# USBdevice.net
KiCad netlist of a schematic drawn in Altium Designer
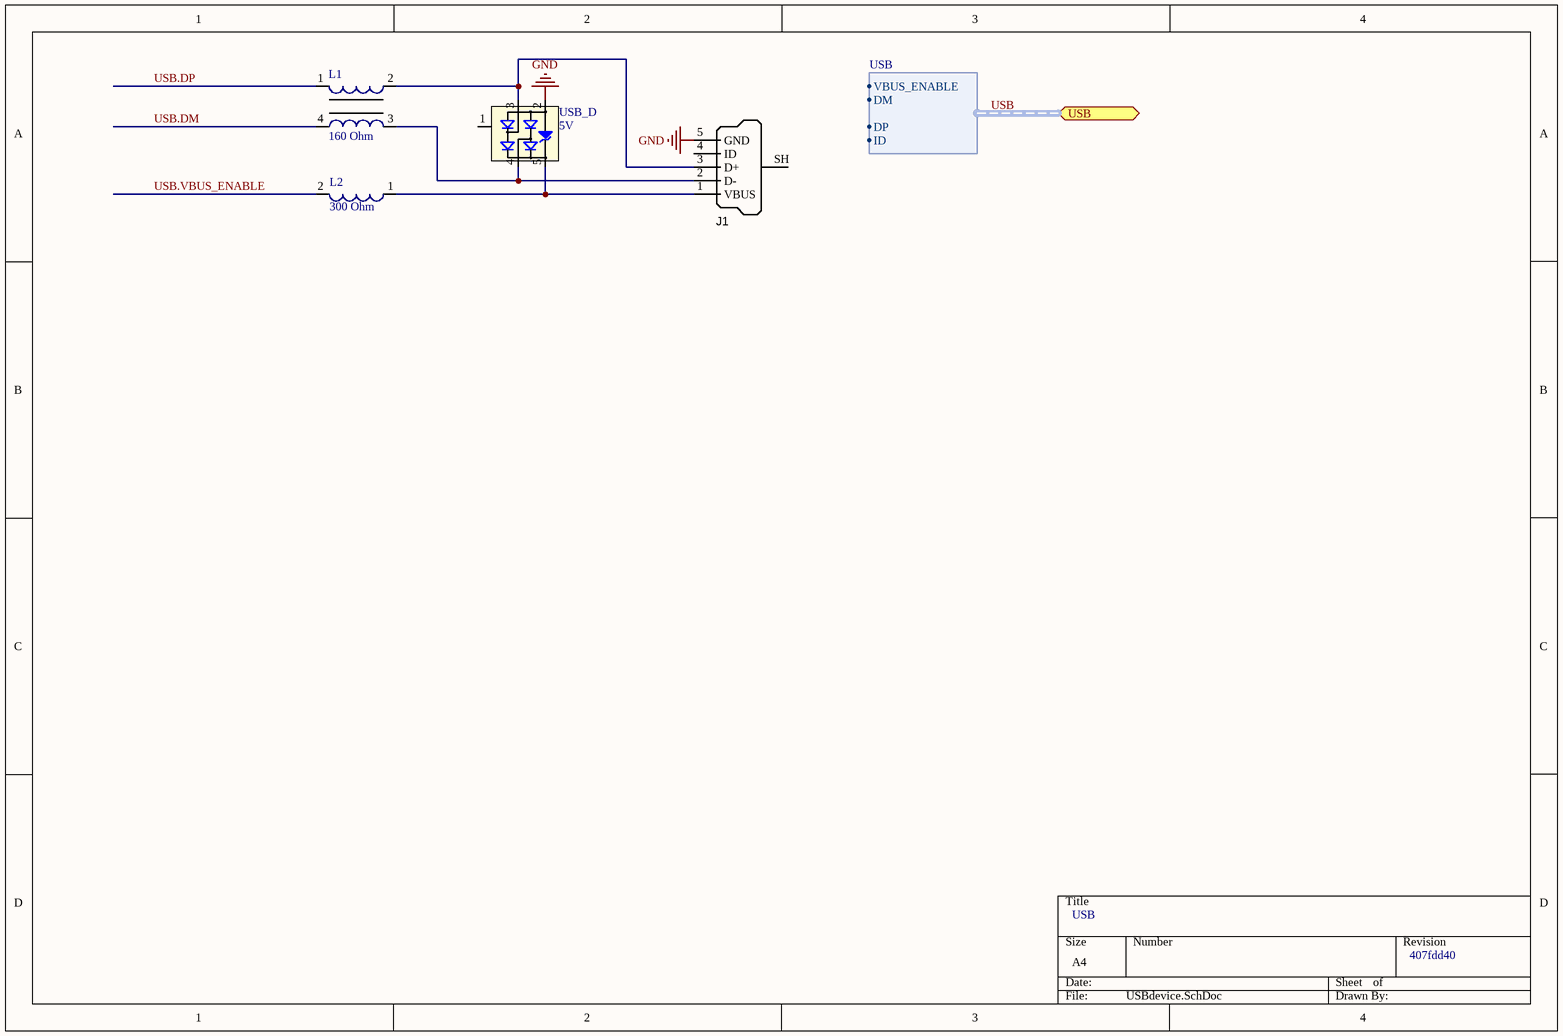
[diagram p0: USBdevice.SchDoc]

(export (version "E")
  (design (tool "Eeschema 10.0.6"))
  (components
    (comp (ref "J1")
      (value "USB Micro Type B")
      (footprint "PBL - SMD Packages:USB_Micro-B_FCI_SMD")
      (description "Connector SMD-THD USB Micro Type B middle mount")
      (libsource (lib "PBL - Connectors") (part "USB_Micro_TypeB_FCI"))
    )
    (comp (ref "L1")
      (value "160 Ohm")
      (footprint "WE-CNSW, 1206")
      (description "SMD Common Mode Noise Suppressor WE-CNSW,  Z= 160 Ohm")
      (fields
        (field (name "PARTNO") "744232161")
        (field (name "MANUFACTURER") "Würth Elektronik eiSos GmbH")
        (field (name "CREATED BY") "Christin Zierenner")
      )
      (libsource (lib "Altium_WE_eiSos_WE-CNSW") (part "WE-CNSW 1206, 744232161"))
    )
    (comp (ref "L2")
      (value "300 Ohm")
      (footprint "SMD 0603")
      (description "SMD EMI Suppression Ferrite Beads WE-CBF, Z= 300 Ohm")
      (fields
        (field (name "PARTNO") "742792641")
        (field (name "MANUFACTURER") "Würth Elektronik eiSos GmbH")
        (field (name "CREATED BY") "Christin Zierenner")
      )
      (libsource (lib "Altium_WE_eiSos_WE-CBF") (part "WE-CBF 0603, 742792641"))
    )
    (comp (ref "USB_D")
      (value "5V")
      (footprint "SOT23_5L")
      (description "TVS Diode WE-TVS-HS, VRWM=5V")
      (fields
        (field (name "PARTNO") "824011")
        (field (name "MANUFACTURER") "Würth Elektronik eiSos GmbH")
        (field (name "CREATED BY") "Christin Zierenner")
      )
      (libsource (lib "WE-TVS") (part "WE-TVS-HS,SOT23-5L,824011"))
    )
  )
  (nets
    (net (code "2") (name "/USB.DM") (class "Default")
      (node (ref "L1") (pin "4") (pinfunction "4_4") (pintype "passive"))
    )
    (net (code "3") (name "/USB.DP") (class "Default")
      (node (ref "L1") (pin "1") (pinfunction "1_1") (pintype "passive"))
    )
    (net (code "4") (name "/USB.VBUS_ENABLE") (class "Default")
      (node (ref "L2") (pin "2") (pinfunction "2_2") (pintype "passive"))
    )
    (net (code "6") (name "GND") (class "Default")
      (node (ref "J1") (pin "5") (pinfunction "GND_5") (pintype "passive"))
      (node (ref "USB_D") (pin "2") (pinfunction "GND_2") (pintype "passive"))
    )
    (net (code "7") (name "Net-(J1-D+)") (class "Default")
      (node (ref "J1") (pin "3") (pinfunction "D+_3") (pintype "passive"))
      (node (ref "L1") (pin "2") (pinfunction "2_2") (pintype "passive"))
      (node (ref "USB_D") (pin "3") (pinfunction "I/O1_3") (pintype "passive"))
    )
    (net (code "8") (name "Net-(J1-D-)") (class "Default")
      (node (ref "J1") (pin "2") (pinfunction "D-_2") (pintype "passive"))
      (node (ref "L1") (pin "3") (pinfunction "3_3") (pintype "passive"))
      (node (ref "USB_D") (pin "4") (pinfunction "I/O2_4") (pintype "passive"))
    )
    (net (code "9") (name "Net-(J1-VBUS)") (class "Default")
      (node (ref "J1") (pin "1") (pinfunction "VBUS_1") (pintype "passive"))
      (node (ref "L2") (pin "1") (pinfunction "1_1") (pintype "passive"))
      (node (ref "USB_D") (pin "5") (pinfunction "VDD_5") (pintype "passive"))
    )
    (net (code "10") (name "unconnected-(J1-ID-Pad4)") (class "Default")
      (node (ref "J1") (pin "4") (pinfunction "ID_4") (pintype "passive"))
    )
    (net (code "11") (name "unconnected-(J1-Shell-PadSH)") (class "Default")
      (node (ref "J1") (pin "SH") (pinfunction "Shell_SH") (pintype "passive"))
    )
    (net (code "12") (name "unconnected-(USB_D-NC-Pad1)") (class "Default")
      (node (ref "USB_D") (pin "1") (pinfunction "NC_1") (pintype "passive"))
    )
  )
)
